# Power_Amp_V2_0.net
KiCad netlist of a schematic drawn in EAGLE
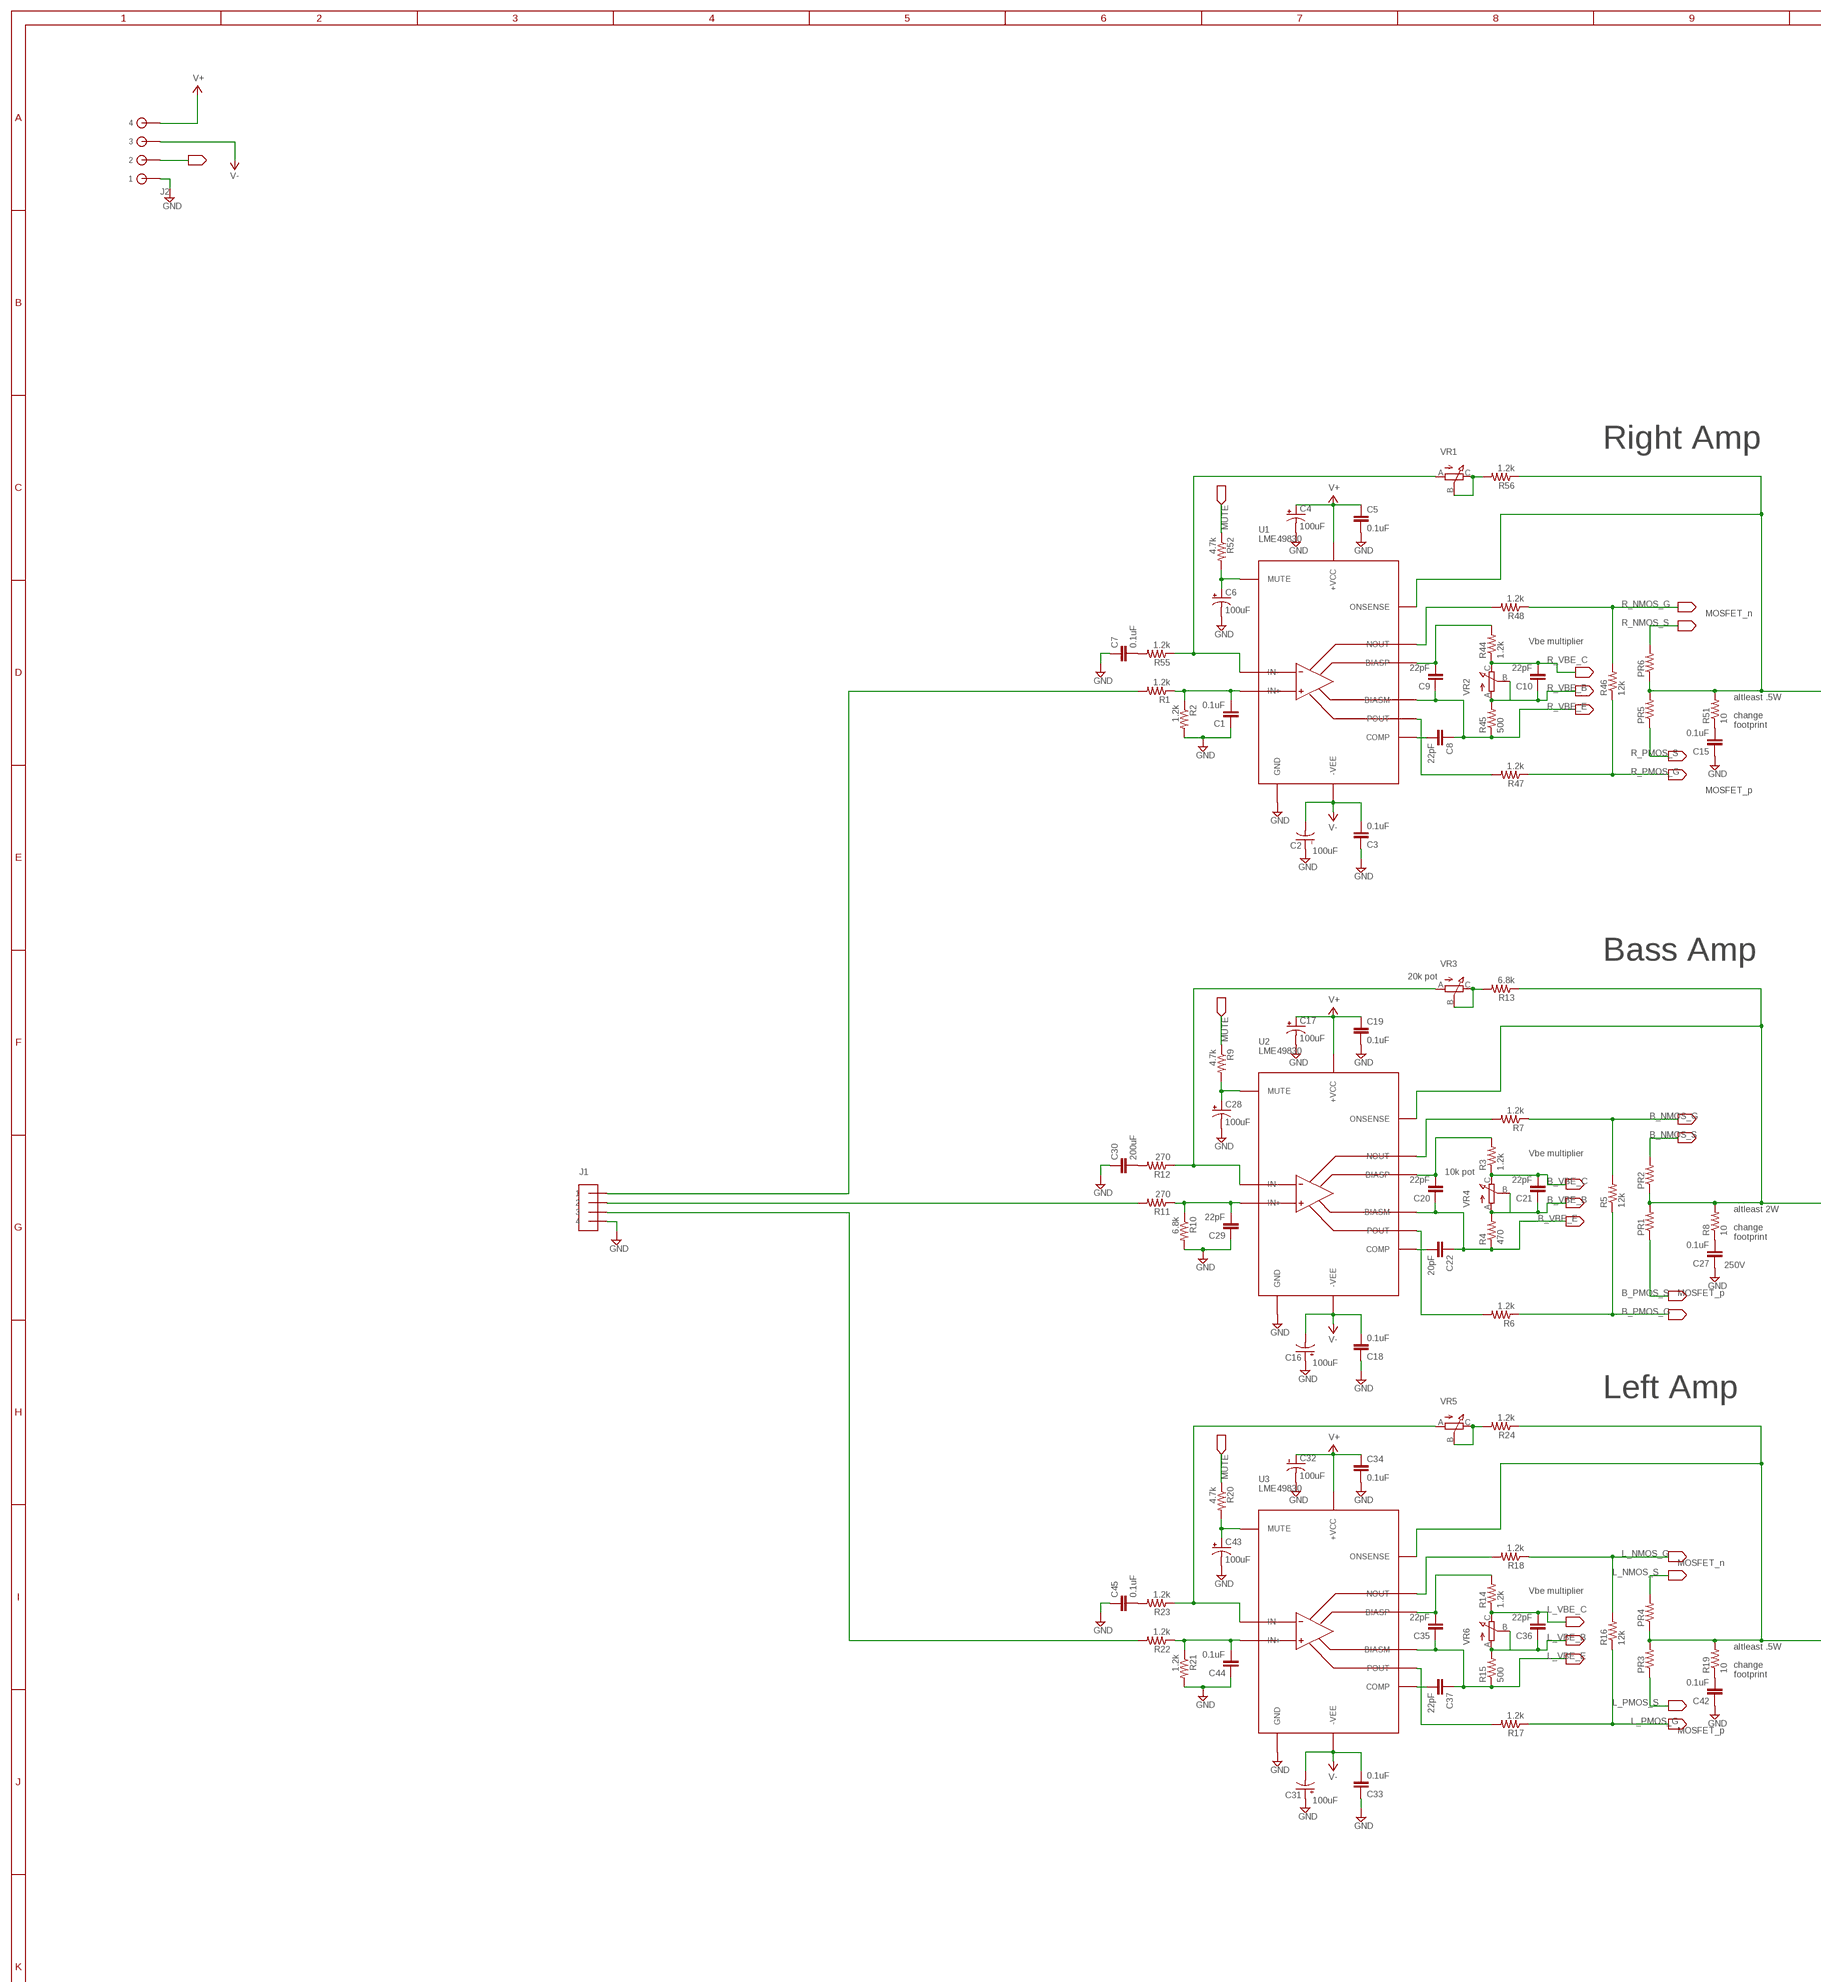
[diagram p0: schematic, sheet 1, part 1 of 3]
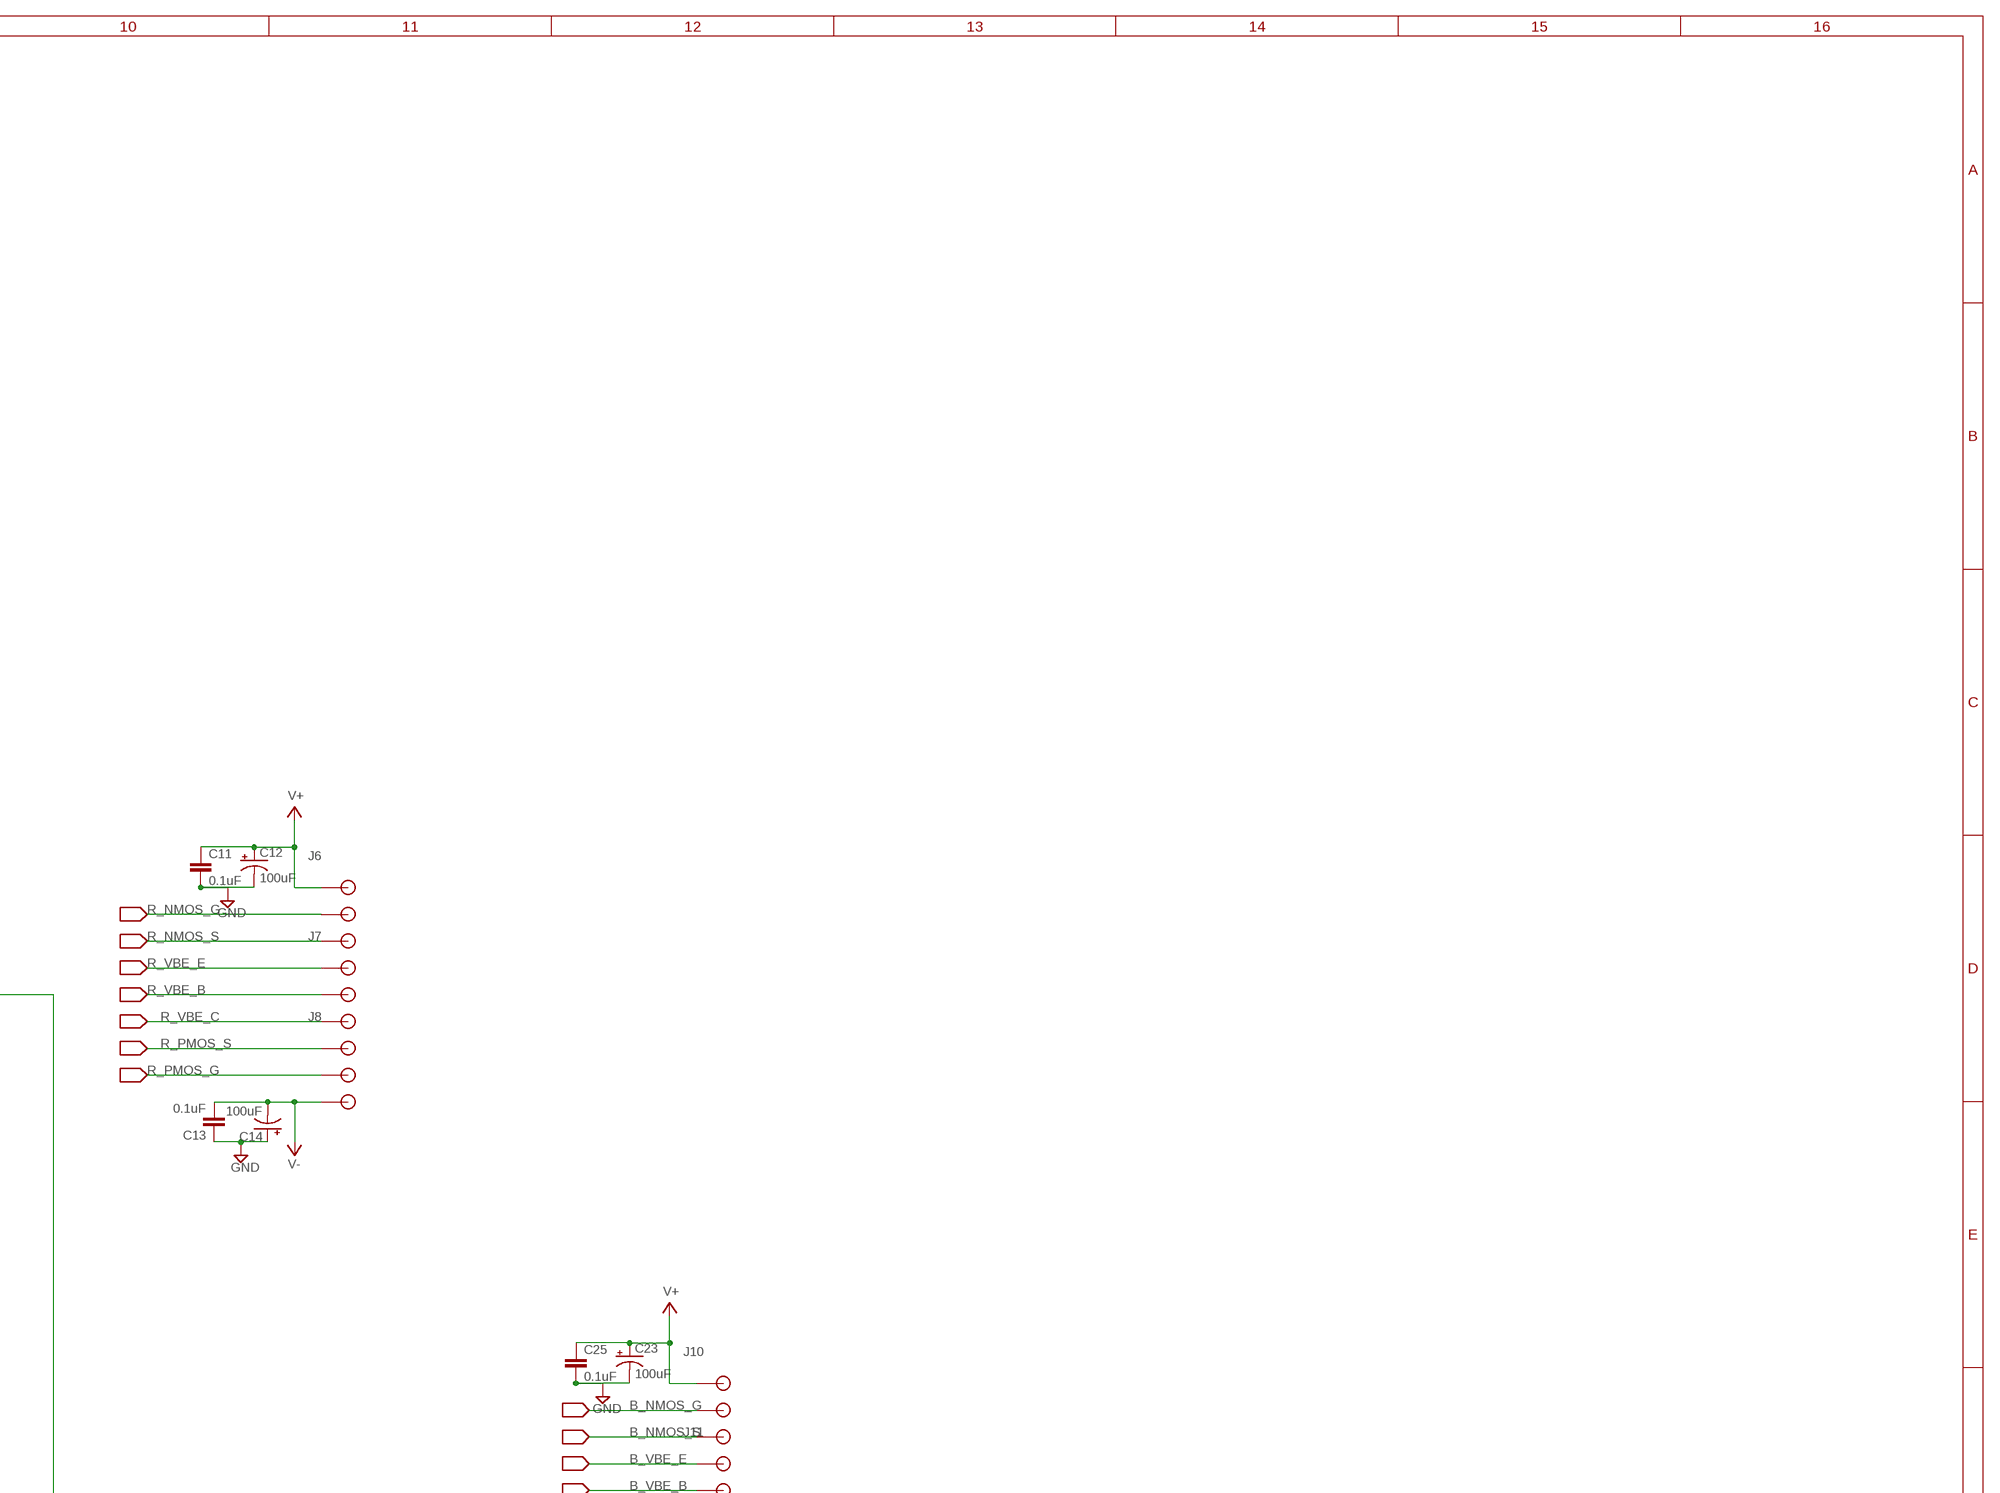
[diagram p1: schematic, sheet 1, part 2 of 3]
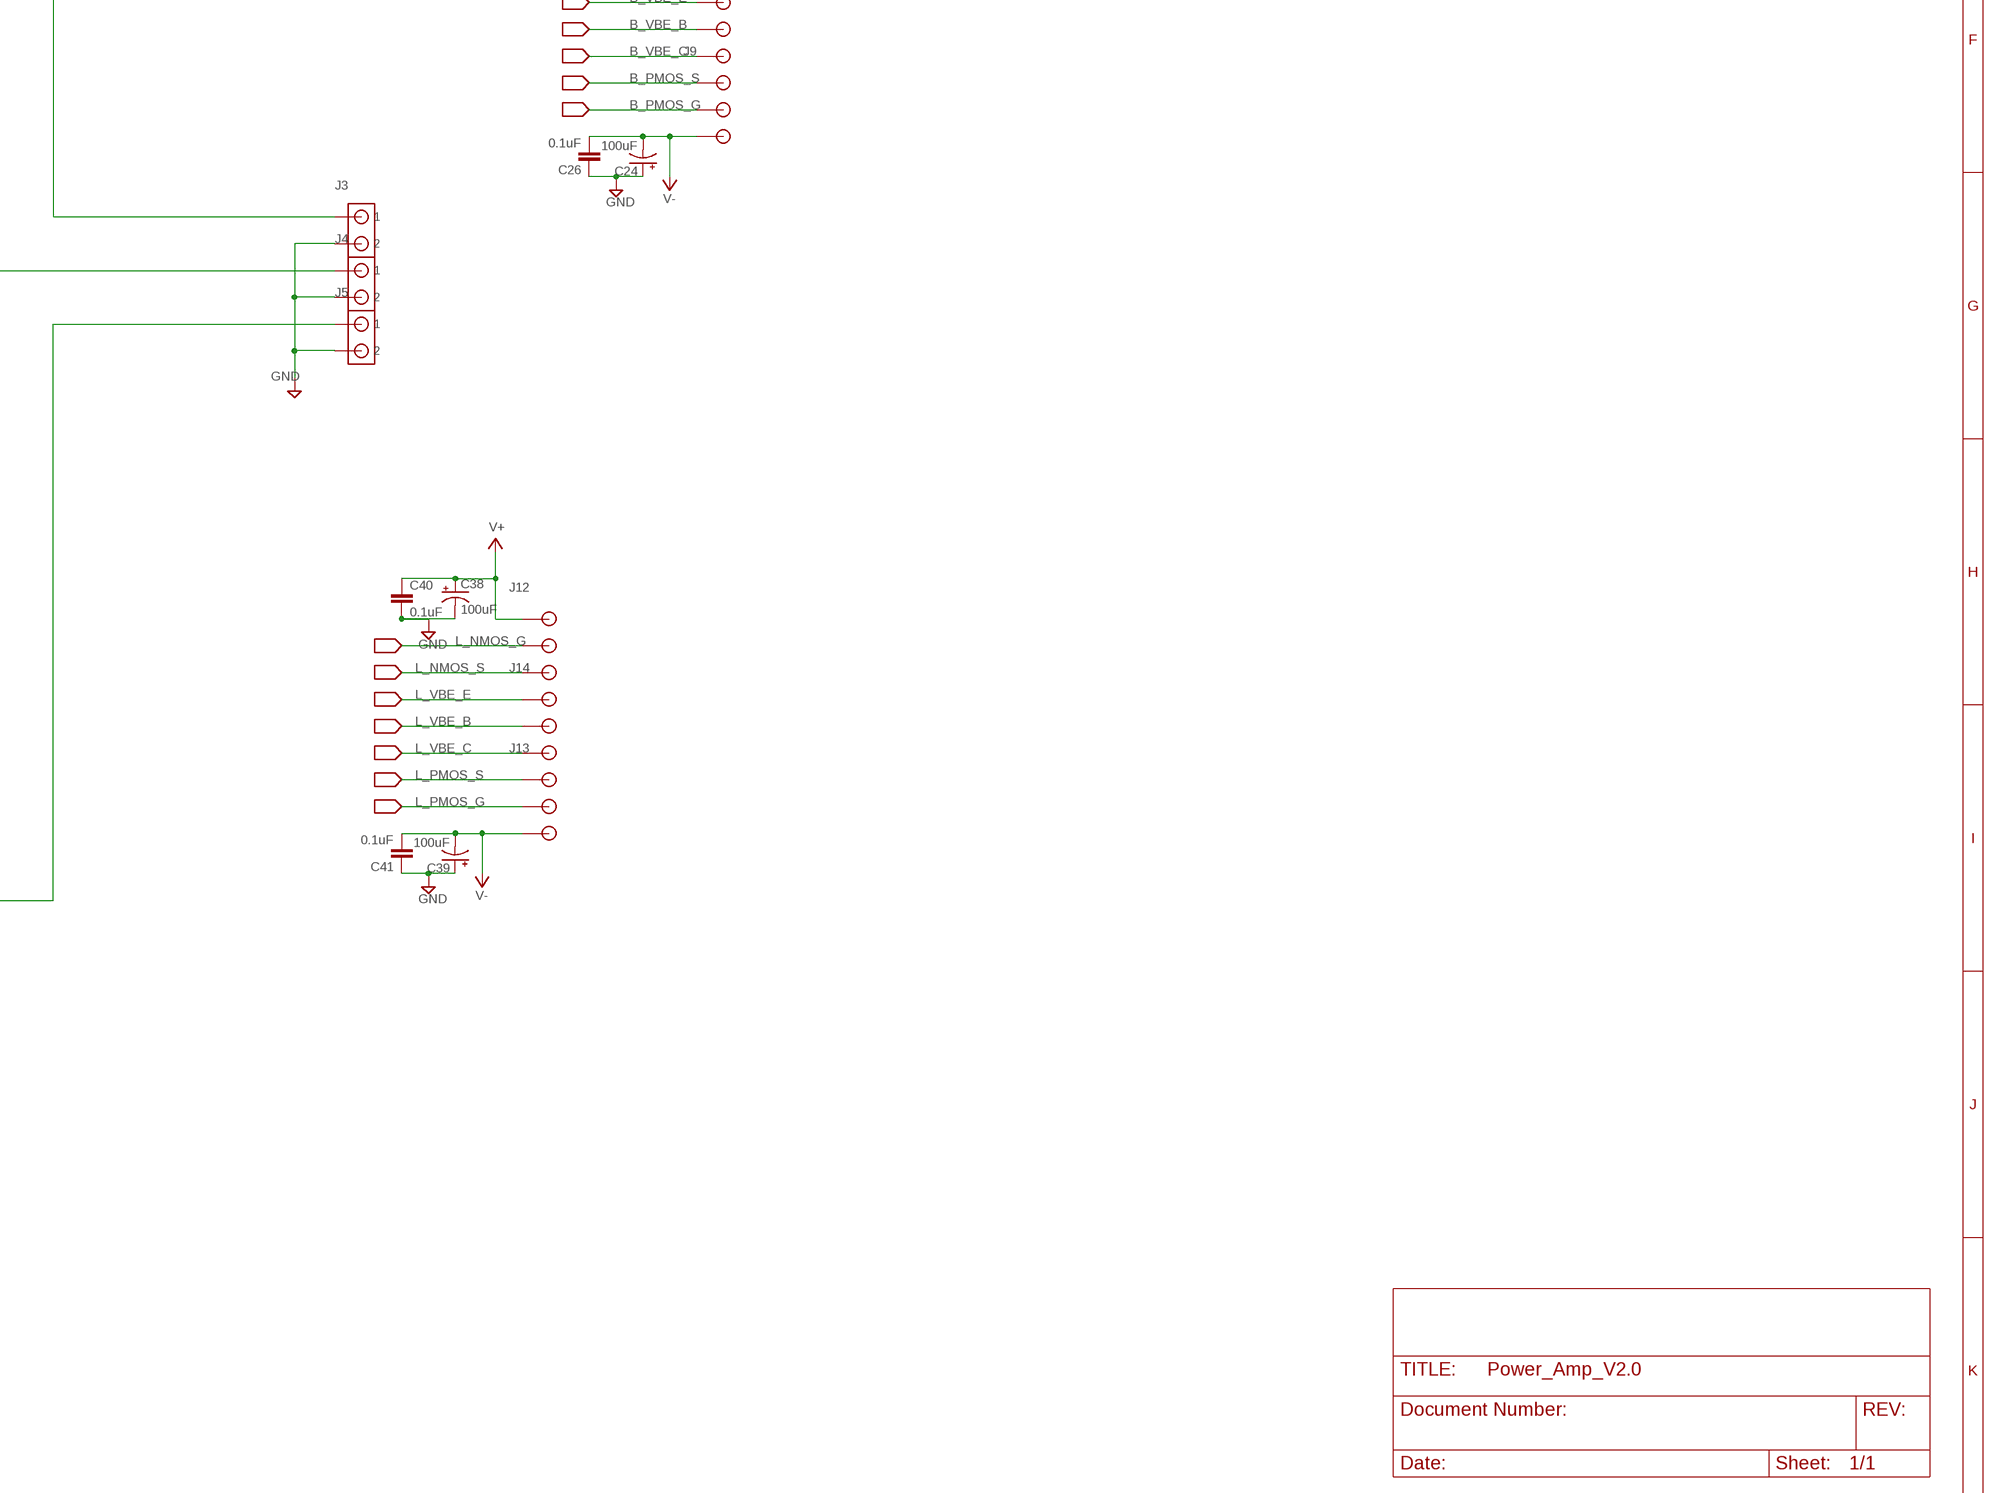
[diagram p2: schematic, sheet 1, part 3 of 3]

(export (version "E")
  (design (tool "Eeschema 10.0.6"))
  (components
    (comp (ref "C1")
      (value "0.1uF")
      (footprint "eagle-import:C050-024X044")
      (libsource (lib "eagle-import") (part "C-EU050-024X044"))
    )
    (comp (ref "C2")
      (value "100uF")
      (footprint "eagle-import:E2,5-6")
      (libsource (lib "eagle-import") (part "CPOL-USE2.5-6"))
    )
    (comp (ref "C3")
      (value "0.1uF")
      (footprint "eagle-import:C050-024X044")
      (libsource (lib "eagle-import") (part "C-EU050-024X044"))
    )
    (comp (ref "C4")
      (value "100uF")
      (footprint "eagle-import:E2,5-6")
      (libsource (lib "eagle-import") (part "CPOL-USE2.5-6"))
    )
    (comp (ref "C5")
      (value "0.1uF")
      (footprint "eagle-import:C050-024X044")
      (libsource (lib "eagle-import") (part "C-EU050-024X044"))
    )
    (comp (ref "C6")
      (value "100uF")
      (footprint "eagle-import:E2,5-6")
      (libsource (lib "eagle-import") (part "CPOL-USE2.5-6"))
    )
    (comp (ref "C7")
      (value "0.1uF")
      (footprint "eagle-import:C050-024X044")
      (libsource (lib "eagle-import") (part "C-EU050-024X044"))
    )
    (comp (ref "C8")
      (value "22pF")
      (footprint "eagle-import:C050-024X044")
      (libsource (lib "eagle-import") (part "C-EU050-024X044"))
    )
    (comp (ref "C9")
      (value "22pF")
      (footprint "eagle-import:C050-024X044")
      (libsource (lib "eagle-import") (part "C-EU050-024X044"))
    )
    (comp (ref "C10")
      (value "22pF")
      (footprint "eagle-import:C050-024X044")
      (libsource (lib "eagle-import") (part "C-EU050-024X044"))
    )
    (comp (ref "C11")
      (value "0.1uF")
      (footprint "eagle-import:C050-024X044")
      (libsource (lib "eagle-import") (part "C-EU050-024X044"))
    )
    (comp (ref "C12")
      (value "100uF")
      (footprint "eagle-import:E2,5-6")
      (libsource (lib "eagle-import") (part "CPOL-USE2.5-6"))
    )
    (comp (ref "C13")
      (value "0.1uF")
      (footprint "eagle-import:C050-024X044")
      (libsource (lib "eagle-import") (part "C-EU050-024X044"))
    )
    (comp (ref "C14")
      (value "100uF")
      (footprint "eagle-import:E2,5-6")
      (libsource (lib "eagle-import") (part "CPOL-USE2.5-6"))
    )
    (comp (ref "C15")
      (value "0.1uF")
      (footprint "eagle-import:C050-024X044")
      (libsource (lib "eagle-import") (part "C-EU050-024X044"))
    )
    (comp (ref "C16")
      (value "100uF")
      (footprint "eagle-import:E2,5-6")
      (libsource (lib "eagle-import") (part "CPOL-USE2.5-6"))
    )
    (comp (ref "C17")
      (value "100uF")
      (footprint "eagle-import:E2,5-6")
      (libsource (lib "eagle-import") (part "CPOL-USE2.5-6"))
    )
    (comp (ref "C18")
      (value "0.1uF")
      (footprint "eagle-import:C050-024X044")
      (libsource (lib "eagle-import") (part "C-EU050-024X044"))
    )
    (comp (ref "C19")
      (value "0.1uF")
      (footprint "eagle-import:C050-024X044")
      (libsource (lib "eagle-import") (part "C-EU050-024X044"))
    )
    (comp (ref "C20")
      (value "22pF")
      (footprint "eagle-import:C050-024X044")
      (libsource (lib "eagle-import") (part "C-EU050-024X044"))
    )
    (comp (ref "C21")
      (value "22pF")
      (footprint "eagle-import:C050-024X044")
      (libsource (lib "eagle-import") (part "C-EU050-024X044"))
    )
    (comp (ref "C22")
      (value "20pF")
      (footprint "eagle-import:C050-024X044")
      (libsource (lib "eagle-import") (part "C-EU050-024X044"))
    )
    (comp (ref "C23")
      (value "100uF")
      (footprint "eagle-import:E2,5-6")
      (libsource (lib "eagle-import") (part "CPOL-USE2.5-6"))
    )
    (comp (ref "C24")
      (value "100uF")
      (footprint "eagle-import:E2,5-6")
      (libsource (lib "eagle-import") (part "CPOL-USE2.5-6"))
    )
    (comp (ref "C25")
      (value "0.1uF")
      (footprint "eagle-import:C050-024X044")
      (libsource (lib "eagle-import") (part "C-EU050-024X044"))
    )
    (comp (ref "C26")
      (value "0.1uF")
      (footprint "eagle-import:C050-024X044")
      (libsource (lib "eagle-import") (part "C-EU050-024X044"))
    )
    (comp (ref "C27")
      (value "0.1uF")
      (footprint "eagle-import:C050-024X044")
      (libsource (lib "eagle-import") (part "C-EU050-024X044"))
    )
    (comp (ref "C28")
      (value "100uF")
      (footprint "eagle-import:E2,5-6")
      (libsource (lib "eagle-import") (part "CPOL-USE2.5-6"))
    )
    (comp (ref "C29")
      (value "22pF")
      (footprint "eagle-import:C050-024X044")
      (libsource (lib "eagle-import") (part "C-EU050-024X044"))
    )
    (comp (ref "C30")
      (value "200uF")
      (footprint "eagle-import:C050-024X044")
      (libsource (lib "eagle-import") (part "C-EU050-024X044"))
    )
    (comp (ref "C31")
      (value "100uF")
      (footprint "eagle-import:E2,5-6")
      (libsource (lib "eagle-import") (part "CPOL-USE2.5-6"))
    )
    (comp (ref "C32")
      (value "100uF")
      (footprint "eagle-import:E2,5-6")
      (libsource (lib "eagle-import") (part "CPOL-USE2.5-6"))
    )
    (comp (ref "C33")
      (value "0.1uF")
      (footprint "eagle-import:C050-024X044")
      (libsource (lib "eagle-import") (part "C-EU050-024X044"))
    )
    (comp (ref "C34")
      (value "0.1uF")
      (footprint "eagle-import:C050-024X044")
      (libsource (lib "eagle-import") (part "C-EU050-024X044"))
    )
    (comp (ref "C35")
      (value "22pF")
      (footprint "eagle-import:C050-024X044")
      (libsource (lib "eagle-import") (part "C-EU050-024X044"))
    )
    (comp (ref "C36")
      (value "22pF")
      (footprint "eagle-import:C050-024X044")
      (libsource (lib "eagle-import") (part "C-EU050-024X044"))
    )
    (comp (ref "C37")
      (value "22pF")
      (footprint "eagle-import:C050-024X044")
      (libsource (lib "eagle-import") (part "C-EU050-024X044"))
    )
    (comp (ref "C38")
      (value "100uF")
      (footprint "eagle-import:E2,5-6")
      (libsource (lib "eagle-import") (part "CPOL-USE2.5-6"))
    )
    (comp (ref "C39")
      (value "100uF")
      (footprint "eagle-import:E2,5-6")
      (libsource (lib "eagle-import") (part "CPOL-USE2.5-6"))
    )
    (comp (ref "C40")
      (value "0.1uF")
      (footprint "eagle-import:C050-024X044")
      (libsource (lib "eagle-import") (part "C-EU050-024X044"))
    )
    (comp (ref "C41")
      (value "0.1uF")
      (footprint "eagle-import:C050-024X044")
      (libsource (lib "eagle-import") (part "C-EU050-024X044"))
    )
    (comp (ref "C42")
      (value "0.1uF")
      (footprint "eagle-import:C050-024X044")
      (libsource (lib "eagle-import") (part "C-EU050-024X044"))
    )
    (comp (ref "C43")
      (value "100uF")
      (footprint "eagle-import:E2,5-6")
      (libsource (lib "eagle-import") (part "CPOL-USE2.5-6"))
    )
    (comp (ref "C44")
      (value "0.1uF")
      (footprint "eagle-import:C050-024X044")
      (libsource (lib "eagle-import") (part "C-EU050-024X044"))
    )
    (comp (ref "C45")
      (value "0.1uF")
      (footprint "eagle-import:C050-024X044")
      (libsource (lib "eagle-import") (part "C-EU050-024X044"))
    )
    (comp (ref "J1")
      (value "4_PIN_AMPCONN")
      (footprint "eagle-import:4_PIN_AMPCON")
      (libsource (lib "eagle-import") (part "4_PIN_AMPCONN"))
    )
    (comp (ref "J2")
      (value "1984633")
      (footprint "eagle-import:1984633")
      (libsource (lib "eagle-import") (part "1984633"))
    )
    (comp (ref "J3")
      (value "2TERMINAL_SPEAKER")
      (footprint "eagle-import:2TERMINAL_SPEAKER")
      (libsource (lib "eagle-import") (part "2TERMINAL_SPEAKER"))
    )
    (comp (ref "J4")
      (value "2TERMINAL_SPEAKER")
      (footprint "eagle-import:2TERMINAL_SPEAKER")
      (libsource (lib "eagle-import") (part "2TERMINAL_SPEAKER"))
    )
    (comp (ref "J5")
      (value "2TERMINAL_SPEAKER")
      (footprint "eagle-import:2TERMINAL_SPEAKER")
      (libsource (lib "eagle-import") (part "2TERMINAL_SPEAKER"))
    )
    (comp (ref "J6")
      (value "OSTVN03A150")
      (footprint "eagle-import:OSTVN03A150")
      (libsource (lib "eagle-import") (part "OSTVN03A150"))
    )
    (comp (ref "J7")
      (value "OSTVN03A150")
      (footprint "eagle-import:OSTVN03A150")
      (libsource (lib "eagle-import") (part "OSTVN03A150"))
    )
    (comp (ref "J8")
      (value "OSTVN03A150")
      (footprint "eagle-import:OSTVN03A150")
      (libsource (lib "eagle-import") (part "OSTVN03A150"))
    )
    (comp (ref "J9")
      (value "OSTVN03A150")
      (footprint "eagle-import:OSTVN03A150")
      (libsource (lib "eagle-import") (part "OSTVN03A150"))
    )
    (comp (ref "J10")
      (value "OSTVN03A150")
      (footprint "eagle-import:OSTVN03A150")
      (libsource (lib "eagle-import") (part "OSTVN03A150"))
    )
    (comp (ref "J11")
      (value "OSTVN03A150")
      (footprint "eagle-import:OSTVN03A150")
      (libsource (lib "eagle-import") (part "OSTVN03A150"))
    )
    (comp (ref "J12")
      (value "OSTVN03A150")
      (footprint "eagle-import:OSTVN03A150")
      (libsource (lib "eagle-import") (part "OSTVN03A150"))
    )
    (comp (ref "J13")
      (value "OSTVN03A150")
      (footprint "eagle-import:OSTVN03A150")
      (libsource (lib "eagle-import") (part "OSTVN03A150"))
    )
    (comp (ref "J14")
      (value "OSTVN03A150")
      (footprint "eagle-import:OSTVN03A150")
      (libsource (lib "eagle-import") (part "OSTVN03A150"))
    )
    (comp (ref "PR1")
      (value "R-US_0617/5V")
      (footprint "eagle-import:0617V")
      (libsource (lib "eagle-import") (part "R-US_0617/5V"))
    )
    (comp (ref "PR2")
      (value "R-US_0617/5V")
      (footprint "eagle-import:0617V")
      (libsource (lib "eagle-import") (part "R-US_0617/5V"))
    )
    (comp (ref "PR3")
      (value "R-US_0617/5V")
      (footprint "eagle-import:0617V")
      (libsource (lib "eagle-import") (part "R-US_0617/5V"))
    )
    (comp (ref "PR4")
      (value "R-US_0617/5V")
      (footprint "eagle-import:0617V")
      (libsource (lib "eagle-import") (part "R-US_0617/5V"))
    )
    (comp (ref "PR5")
      (value "R-US_0617/5V")
      (footprint "eagle-import:0617V")
      (libsource (lib "eagle-import") (part "R-US_0617/5V"))
    )
    (comp (ref "PR6")
      (value "R-US_0617/5V")
      (footprint "eagle-import:0617V")
      (libsource (lib "eagle-import") (part "R-US_0617/5V"))
    )
    (comp (ref "R1")
      (value "1.2k")
      (footprint "eagle-import:0204V")
      (libsource (lib "eagle-import") (part "R-US_0204/2V"))
    )
    (comp (ref "R2")
      (value "1.2k")
      (footprint "eagle-import:0204V")
      (libsource (lib "eagle-import") (part "R-US_0204/2V"))
    )
    (comp (ref "R3")
      (value "1.2k")
      (footprint "eagle-import:0204V")
      (libsource (lib "eagle-import") (part "R-US_0204/2V"))
    )
    (comp (ref "R4")
      (value "470")
      (footprint "eagle-import:0204V")
      (libsource (lib "eagle-import") (part "R-US_0204/2V"))
    )
    (comp (ref "R5")
      (value "12k")
      (footprint "eagle-import:0204V")
      (libsource (lib "eagle-import") (part "R-US_0204/2V"))
    )
    (comp (ref "R6")
      (value "1.2k")
      (footprint "eagle-import:0204V")
      (libsource (lib "eagle-import") (part "R-US_0204/2V"))
    )
    (comp (ref "R7")
      (value "1.2k")
      (footprint "eagle-import:0204V")
      (libsource (lib "eagle-import") (part "R-US_0204/2V"))
    )
    (comp (ref "R8")
      (value "10")
      (footprint "eagle-import:0309V")
      (libsource (lib "eagle-import") (part "R-US_0309/V"))
    )
    (comp (ref "R9")
      (value "4.7k")
      (footprint "eagle-import:0204V")
      (libsource (lib "eagle-import") (part "R-US_0204/2V"))
    )
    (comp (ref "R10")
      (value "6.8k")
      (footprint "eagle-import:0204V")
      (libsource (lib "eagle-import") (part "R-US_0204/2V"))
    )
    (comp (ref "R11")
      (value "270")
      (footprint "eagle-import:0204V")
      (libsource (lib "eagle-import") (part "R-US_0204/2V"))
    )
    (comp (ref "R12")
      (value "270")
      (footprint "eagle-import:0204V")
      (libsource (lib "eagle-import") (part "R-US_0204/2V"))
    )
    (comp (ref "R13")
      (value "6.8k")
      (footprint "eagle-import:0204V")
      (libsource (lib "eagle-import") (part "R-US_0204/2V"))
    )
    (comp (ref "R14")
      (value "1.2k")
      (footprint "eagle-import:0204V")
      (libsource (lib "eagle-import") (part "R-US_0204/2V"))
    )
    (comp (ref "R15")
      (value "500")
      (footprint "eagle-import:0204V")
      (libsource (lib "eagle-import") (part "R-US_0204/2V"))
    )
    (comp (ref "R16")
      (value "12k")
      (footprint "eagle-import:0204V")
      (libsource (lib "eagle-import") (part "R-US_0204/2V"))
    )
    (comp (ref "R17")
      (value "1.2k")
      (footprint "eagle-import:0204V")
      (libsource (lib "eagle-import") (part "R-US_0204/2V"))
    )
    (comp (ref "R18")
      (value "1.2k")
      (footprint "eagle-import:0204V")
      (libsource (lib "eagle-import") (part "R-US_0204/2V"))
    )
    (comp (ref "R19")
      (value "10")
      (footprint "eagle-import:0309V")
      (libsource (lib "eagle-import") (part "R-US_0309/V"))
    )
    (comp (ref "R20")
      (value "4.7k")
      (footprint "eagle-import:0204V")
      (libsource (lib "eagle-import") (part "R-US_0204/2V"))
    )
    (comp (ref "R21")
      (value "1.2k")
      (footprint "eagle-import:0204V")
      (libsource (lib "eagle-import") (part "R-US_0204/2V"))
    )
    (comp (ref "R22")
      (value "1.2k")
      (footprint "eagle-import:0204V")
      (libsource (lib "eagle-import") (part "R-US_0204/2V"))
    )
    (comp (ref "R23")
      (value "1.2k")
      (footprint "eagle-import:0204V")
      (libsource (lib "eagle-import") (part "R-US_0204/2V"))
    )
    (comp (ref "R24")
      (value "1.2k")
      (footprint "eagle-import:0204V")
      (libsource (lib "eagle-import") (part "R-US_0204/2V"))
    )
    (comp (ref "R44")
      (value "1.2k")
      (footprint "eagle-import:0204V")
      (libsource (lib "eagle-import") (part "R-US_0204/2V"))
    )
    (comp (ref "R45")
      (value "500")
      (footprint "eagle-import:0204V")
      (libsource (lib "eagle-import") (part "R-US_0204/2V"))
    )
    (comp (ref "R46")
      (value "12k")
      (footprint "eagle-import:0204V")
      (libsource (lib "eagle-import") (part "R-US_0204/2V"))
    )
    (comp (ref "R47")
      (value "1.2k")
      (footprint "eagle-import:0204V")
      (libsource (lib "eagle-import") (part "R-US_0204/2V"))
    )
    (comp (ref "R48")
      (value "1.2k")
      (footprint "eagle-import:0204V")
      (libsource (lib "eagle-import") (part "R-US_0204/2V"))
    )
    (comp (ref "R51")
      (value "10")
      (footprint "eagle-import:0309V")
      (libsource (lib "eagle-import") (part "R-US_0309/V"))
    )
    (comp (ref "R52")
      (value "4.7k")
      (footprint "eagle-import:0204V")
      (libsource (lib "eagle-import") (part "R-US_0204/2V"))
    )
    (comp (ref "R55")
      (value "1.2k")
      (footprint "eagle-import:0204V")
      (libsource (lib "eagle-import") (part "R-US_0204/2V"))
    )
    (comp (ref "R56")
      (value "1.2k")
      (footprint "eagle-import:0204V")
      (libsource (lib "eagle-import") (part "R-US_0204/2V"))
    )
    (comp (ref "U1")
      (value "LME49830")
      (footprint "eagle-import:NDN0015A")
      (libsource (lib "eagle-import") (part "LME49830"))
    )
    (comp (ref "U2")
      (value "LME49830")
      (footprint "eagle-import:NDN0015A")
      (libsource (lib "eagle-import") (part "LME49830"))
    )
    (comp (ref "U3")
      (value "LME49830")
      (footprint "eagle-import:NDN0015A")
      (libsource (lib "eagle-import") (part "LME49830"))
    )
    (comp (ref "VR1")
      (value "EVM2W")
      (footprint "eagle-import:EVM2W")
      (libsource (lib "eagle-import") (part "EVM2W"))
    )
    (comp (ref "VR2")
      (value "EVM2W")
      (footprint "eagle-import:EVM2W")
      (libsource (lib "eagle-import") (part "EVM2W"))
    )
    (comp (ref "VR3")
      (value "EVM2W")
      (footprint "eagle-import:EVM2W")
      (libsource (lib "eagle-import") (part "EVM2W"))
    )
    (comp (ref "VR4")
      (value "EVM2W")
      (footprint "eagle-import:EVM2W")
      (libsource (lib "eagle-import") (part "EVM2W"))
    )
    (comp (ref "VR5")
      (value "EVM2W")
      (footprint "eagle-import:EVM2W")
      (libsource (lib "eagle-import") (part "EVM2W"))
    )
    (comp (ref "VR6")
      (value "EVM2W")
      (footprint "eagle-import:EVM2W")
      (libsource (lib "eagle-import") (part "EVM2W"))
    )
  )
  (nets
    (net (code "1") (name "/B_NMOS_G") (class "Default")
      (node (ref "J10") (pin "P$2") (pinfunction "2_P$2") (pintype "bidirectional"))
      (node (ref "R5") (pin "2") (pinfunction "2_2") (pintype "passive"))
      (node (ref "R7") (pin "1") (pinfunction "1_1") (pintype "passive"))
    )
    (net (code "2") (name "/B_NMOS_S") (class "Default")
      (node (ref "J10") (pin "P$3") (pinfunction "3_P$3") (pintype "bidirectional"))
      (node (ref "PR2") (pin "2") (pinfunction "2_2") (pintype "passive"))
    )
    (net (code "3") (name "/B_PMOS_G") (class "Default")
      (node (ref "J9") (pin "P$2") (pinfunction "2_P$2") (pintype "bidirectional"))
      (node (ref "R5") (pin "1") (pinfunction "1_1") (pintype "passive"))
      (node (ref "R6") (pin "1") (pinfunction "1_1") (pintype "passive"))
    )
    (net (code "4") (name "/B_PMOS_S") (class "Default")
      (node (ref "J9") (pin "P$1") (pinfunction "1_P$1") (pintype "bidirectional"))
      (node (ref "PR1") (pin "1") (pinfunction "1_1") (pintype "passive"))
    )
    (net (code "5") (name "/B_VBE_B") (class "Default")
      (node (ref "C21") (pin "1") (pinfunction "1_1") (pintype "passive"))
      (node (ref "J11") (pin "P$2") (pinfunction "2_P$2") (pintype "bidirectional"))
      (node (ref "R4") (pin "2") (pinfunction "2_2") (pintype "passive"))
      (node (ref "VR4") (pin "A") (pinfunction "A_A") (pintype "passive"))
      (node (ref "VR4") (pin "B") (pinfunction "B_B") (pintype "passive"))
    )
    (net (code "6") (name "/B_VBE_C") (class "Default")
      (node (ref "C21") (pin "2") (pinfunction "2_2") (pintype "passive"))
      (node (ref "J11") (pin "P$3") (pinfunction "3_P$3") (pintype "bidirectional"))
      (node (ref "R3") (pin "1") (pinfunction "1_1") (pintype "passive"))
      (node (ref "VR4") (pin "C") (pinfunction "C_C") (pintype "passive"))
    )
    (net (code "7") (name "/B_VBE_E") (class "Default")
      (node (ref "C20") (pin "1") (pinfunction "1_1") (pintype "passive"))
      (node (ref "C22") (pin "1") (pinfunction "1_1") (pintype "passive"))
      (node (ref "J11") (pin "P$1") (pinfunction "1_P$1") (pintype "bidirectional"))
      (node (ref "R4") (pin "1") (pinfunction "1_1") (pintype "passive"))
      (node (ref "U2") (pin "P11") (pinfunction "BIASM_P11") (pintype "bidirectional"))
    )
    (net (code "8") (name "/L_NMOS_G") (class "Default")
      (node (ref "J12") (pin "P$2") (pinfunction "2_P$2") (pintype "bidirectional"))
      (node (ref "R16") (pin "2") (pinfunction "2_2") (pintype "passive"))
      (node (ref "R18") (pin "1") (pinfunction "1_1") (pintype "passive"))
    )
    (net (code "9") (name "/L_NMOS_S") (class "Default")
      (node (ref "J12") (pin "P$3") (pinfunction "3_P$3") (pintype "bidirectional"))
      (node (ref "PR4") (pin "2") (pinfunction "2_2") (pintype "passive"))
    )
    (net (code "10") (name "/L_PMOS_G") (class "Default")
      (node (ref "J13") (pin "P$2") (pinfunction "2_P$2") (pintype "bidirectional"))
      (node (ref "R16") (pin "1") (pinfunction "1_1") (pintype "passive"))
      (node (ref "R17") (pin "1") (pinfunction "1_1") (pintype "passive"))
    )
    (net (code "11") (name "/L_PMOS_S") (class "Default")
      (node (ref "J13") (pin "P$1") (pinfunction "1_P$1") (pintype "bidirectional"))
      (node (ref "PR3") (pin "1") (pinfunction "1_1") (pintype "passive"))
    )
    (net (code "12") (name "/L_VBE_B") (class "Default")
      (node (ref "C36") (pin "1") (pinfunction "1_1") (pintype "passive"))
      (node (ref "J14") (pin "P$2") (pinfunction "2_P$2") (pintype "bidirectional"))
      (node (ref "R15") (pin "2") (pinfunction "2_2") (pintype "passive"))
      (node (ref "VR6") (pin "A") (pinfunction "A_A") (pintype "passive"))
      (node (ref "VR6") (pin "B") (pinfunction "B_B") (pintype "passive"))
    )
    (net (code "13") (name "/L_VBE_C") (class "Default")
      (node (ref "C36") (pin "2") (pinfunction "2_2") (pintype "passive"))
      (node (ref "J14") (pin "P$3") (pinfunction "3_P$3") (pintype "bidirectional"))
      (node (ref "R14") (pin "1") (pinfunction "1_1") (pintype "passive"))
      (node (ref "VR6") (pin "C") (pinfunction "C_C") (pintype "passive"))
    )
    (net (code "14") (name "/L_VBE_E") (class "Default")
      (node (ref "C35") (pin "1") (pinfunction "1_1") (pintype "passive"))
      (node (ref "C37") (pin "1") (pinfunction "1_1") (pintype "passive"))
      (node (ref "J14") (pin "P$1") (pinfunction "1_P$1") (pintype "bidirectional"))
      (node (ref "R15") (pin "1") (pinfunction "1_1") (pintype "passive"))
      (node (ref "U3") (pin "P11") (pinfunction "BIASM_P11") (pintype "bidirectional"))
    )
    (net (code "15") (name "/MUTE") (class "Default")
      (node (ref "J2") (pin "P$2") (pinfunction "2_P$2") (pintype "passive"))
      (node (ref "R20") (pin "1") (pinfunction "1_1") (pintype "passive"))
      (node (ref "R52") (pin "1") (pinfunction "1_1") (pintype "passive"))
      (node (ref "R9") (pin "1") (pinfunction "1_1") (pintype "passive"))
    )
    (net (code "16") (name "/R_NMOS_G") (class "Default")
      (node (ref "J6") (pin "P$2") (pinfunction "2_P$2") (pintype "bidirectional"))
      (node (ref "R46") (pin "2") (pinfunction "2_2") (pintype "passive"))
      (node (ref "R48") (pin "1") (pinfunction "1_1") (pintype "passive"))
    )
    (net (code "17") (name "/R_NMOS_S") (class "Default")
      (node (ref "J6") (pin "P$3") (pinfunction "3_P$3") (pintype "bidirectional"))
      (node (ref "PR6") (pin "2") (pinfunction "2_2") (pintype "passive"))
    )
    (net (code "18") (name "/R_PMOS_G") (class "Default")
      (node (ref "J8") (pin "P$2") (pinfunction "2_P$2") (pintype "bidirectional"))
      (node (ref "R46") (pin "1") (pinfunction "1_1") (pintype "passive"))
      (node (ref "R47") (pin "1") (pinfunction "1_1") (pintype "passive"))
    )
    (net (code "19") (name "/R_PMOS_S") (class "Default")
      (node (ref "J8") (pin "P$1") (pinfunction "1_P$1") (pintype "bidirectional"))
      (node (ref "PR5") (pin "1") (pinfunction "1_1") (pintype "passive"))
    )
    (net (code "20") (name "/R_VBE_B") (class "Default")
      (node (ref "C10") (pin "1") (pinfunction "1_1") (pintype "passive"))
      (node (ref "J7") (pin "P$2") (pinfunction "2_P$2") (pintype "bidirectional"))
      (node (ref "R45") (pin "2") (pinfunction "2_2") (pintype "passive"))
      (node (ref "VR2") (pin "A") (pinfunction "A_A") (pintype "passive"))
      (node (ref "VR2") (pin "B") (pinfunction "B_B") (pintype "passive"))
    )
    (net (code "21") (name "/R_VBE_C") (class "Default")
      (node (ref "C10") (pin "2") (pinfunction "2_2") (pintype "passive"))
      (node (ref "J7") (pin "P$3") (pinfunction "3_P$3") (pintype "bidirectional"))
      (node (ref "R44") (pin "1") (pinfunction "1_1") (pintype "passive"))
      (node (ref "VR2") (pin "C") (pinfunction "C_C") (pintype "passive"))
    )
    (net (code "22") (name "/R_VBE_E") (class "Default")
      (node (ref "C8") (pin "1") (pinfunction "1_1") (pintype "passive"))
      (node (ref "C9") (pin "1") (pinfunction "1_1") (pintype "passive"))
      (node (ref "J7") (pin "P$1") (pinfunction "1_P$1") (pintype "bidirectional"))
      (node (ref "R45") (pin "1") (pinfunction "1_1") (pintype "passive"))
      (node (ref "U1") (pin "P11") (pinfunction "BIASM_P11") (pintype "bidirectional"))
    )
    (net (code "23") (name "GND") (class "Default")
      (node (ref "C1") (pin "1") (pinfunction "1_1") (pintype "passive"))
      (node (ref "C11") (pin "2") (pinfunction "2_2") (pintype "passive"))
      (node (ref "C12") (pin "-") (pinfunction "-_-") (pintype "passive"))
      (node (ref "C13") (pin "1") (pinfunction "1_1") (pintype "passive"))
      (node (ref "C14") (pin "+") (pinfunction "+_+") (pintype "passive"))
      (node (ref "C15") (pin "1") (pinfunction "1_1") (pintype "passive"))
      (node (ref "C16") (pin "+") (pinfunction "+_+") (pintype "passive"))
      (node (ref "C17") (pin "-") (pinfunction "-_-") (pintype "passive"))
      (node (ref "C18") (pin "1") (pinfunction "1_1") (pintype "passive"))
      (node (ref "C19") (pin "2") (pinfunction "2_2") (pintype "passive"))
      (node (ref "C2") (pin "+") (pinfunction "+_+") (pintype "passive"))
      (node (ref "C23") (pin "-") (pinfunction "-_-") (pintype "passive"))
      (node (ref "C24") (pin "+") (pinfunction "+_+") (pintype "passive"))
      (node (ref "C25") (pin "2") (pinfunction "2_2") (pintype "passive"))
      (node (ref "C26") (pin "1") (pinfunction "1_1") (pintype "passive"))
      (node (ref "C27") (pin "1") (pinfunction "1_1") (pintype "passive"))
      (node (ref "C28") (pin "-") (pinfunction "-_-") (pintype "passive"))
      (node (ref "C29") (pin "1") (pinfunction "1_1") (pintype "passive"))
      (node (ref "C3") (pin "1") (pinfunction "1_1") (pintype "passive"))
      (node (ref "C30") (pin "1") (pinfunction "1_1") (pintype "passive"))
      (node (ref "C31") (pin "+") (pinfunction "+_+") (pintype "passive"))
      (node (ref "C32") (pin "-") (pinfunction "-_-") (pintype "passive"))
      (node (ref "C33") (pin "1") (pinfunction "1_1") (pintype "passive"))
      (node (ref "C34") (pin "2") (pinfunction "2_2") (pintype "passive"))
      (node (ref "C38") (pin "-") (pinfunction "-_-") (pintype "passive"))
      (node (ref "C39") (pin "+") (pinfunction "+_+") (pintype "passive"))
      (node (ref "C4") (pin "-") (pinfunction "-_-") (pintype "passive"))
      (node (ref "C40") (pin "2") (pinfunction "2_2") (pintype "passive"))
      (node (ref "C41") (pin "1") (pinfunction "1_1") (pintype "passive"))
      (node (ref "C42") (pin "1") (pinfunction "1_1") (pintype "passive"))
      (node (ref "C43") (pin "-") (pinfunction "-_-") (pintype "passive"))
      (node (ref "C44") (pin "1") (pinfunction "1_1") (pintype "passive"))
      (node (ref "C45") (pin "1") (pinfunction "1_1") (pintype "passive"))
      (node (ref "C5") (pin "2") (pinfunction "2_2") (pintype "passive"))
      (node (ref "C6") (pin "-") (pinfunction "-_-") (pintype "passive"))
      (node (ref "C7") (pin "1") (pinfunction "1_1") (pintype "passive"))
      (node (ref "J1") (pin "4") (pinfunction "4_4") (pintype "passive"))
      (node (ref "J2") (pin "P$1") (pinfunction "1_P$1") (pintype "passive"))
      (node (ref "J3") (pin "P$2") (pinfunction "2_P$2") (pintype "passive"))
      (node (ref "J4") (pin "P$2") (pinfunction "2_P$2") (pintype "passive"))
      (node (ref "J5") (pin "P$2") (pinfunction "2_P$2") (pintype "passive"))
      (node (ref "R10") (pin "2") (pinfunction "2_2") (pintype "passive"))
      (node (ref "R2") (pin "2") (pinfunction "2_2") (pintype "passive"))
      (node (ref "R21") (pin "2") (pinfunction "2_2") (pintype "passive"))
      (node (ref "U1") (pin "P3") (pinfunction "GND_P3") (pintype "bidirectional"))
      (node (ref "U2") (pin "P3") (pinfunction "GND_P3") (pintype "bidirectional"))
      (node (ref "U3") (pin "P3") (pinfunction "GND_P3") (pintype "bidirectional"))
    )
    (net (code "24") (name "Net-(C7-Pad2)") (class "Default")
      (node (ref "C7") (pin "2") (pinfunction "2_2") (pintype "passive"))
      (node (ref "R55") (pin "2") (pinfunction "2_2") (pintype "passive"))
    )
    (net (code "25") (name "Net-(C15-Pad2)") (class "Default")
      (node (ref "C15") (pin "2") (pinfunction "2_2") (pintype "passive"))
      (node (ref "R51") (pin "1") (pinfunction "1_1") (pintype "passive"))
    )
    (net (code "26") (name "Net-(C27-Pad2)") (class "Default")
      (node (ref "C27") (pin "2") (pinfunction "2_2") (pintype "passive"))
      (node (ref "R8") (pin "1") (pinfunction "1_1") (pintype "passive"))
    )
    (net (code "27") (name "Net-(C30-Pad2)") (class "Default")
      (node (ref "C30") (pin "2") (pinfunction "2_2") (pintype "passive"))
      (node (ref "R12") (pin "2") (pinfunction "2_2") (pintype "passive"))
    )
    (net (code "28") (name "Net-(C42-Pad2)") (class "Default")
      (node (ref "C42") (pin "2") (pinfunction "2_2") (pintype "passive"))
      (node (ref "R19") (pin "1") (pinfunction "1_1") (pintype "passive"))
    )
    (net (code "29") (name "Net-(C45-Pad2)") (class "Default")
      (node (ref "C45") (pin "2") (pinfunction "2_2") (pintype "passive"))
      (node (ref "R23") (pin "2") (pinfunction "2_2") (pintype "passive"))
    )
    (net (code "30") (name "Net-(J1-Pad1)") (class "Default")
      (node (ref "J1") (pin "1") (pinfunction "1_1") (pintype "passive"))
      (node (ref "R1") (pin "2") (pinfunction "2_2") (pintype "passive"))
    )
    (net (code "31") (name "Net-(J1-Pad2)") (class "Default")
      (node (ref "J1") (pin "2") (pinfunction "2_2") (pintype "passive"))
      (node (ref "R11") (pin "2") (pinfunction "2_2") (pintype "passive"))
    )
    (net (code "32") (name "Net-(J1-Pad3)") (class "Default")
      (node (ref "J1") (pin "3") (pinfunction "3_3") (pintype "passive"))
      (node (ref "R22") (pin "2") (pinfunction "2_2") (pintype "passive"))
    )
    (net (code "33") (name "Net-(J3-1)") (class "Default")
      (node (ref "J3") (pin "P$1") (pinfunction "1_P$1") (pintype "passive"))
      (node (ref "PR5") (pin "2") (pinfunction "2_2") (pintype "passive"))
      (node (ref "PR6") (pin "1") (pinfunction "1_1") (pintype "passive"))
      (node (ref "R51") (pin "2") (pinfunction "2_2") (pintype "passive"))
      (node (ref "R56") (pin "1") (pinfunction "1_1") (pintype "passive"))
      (node (ref "U1") (pin "P$8") (pinfunction "ONSENSE_P$8") (pintype "bidirectional"))
    )
    (net (code "34") (name "Net-(J4-1)") (class "Default")
      (node (ref "J4") (pin "P$1") (pinfunction "1_P$1") (pintype "passive"))
      (node (ref "PR1") (pin "2") (pinfunction "2_2") (pintype "passive"))
      (node (ref "PR2") (pin "1") (pinfunction "1_1") (pintype "passive"))
      (node (ref "R13") (pin "1") (pinfunction "1_1") (pintype "passive"))
      (node (ref "R8") (pin "2") (pinfunction "2_2") (pintype "passive"))
      (node (ref "U2") (pin "P$8") (pinfunction "ONSENSE_P$8") (pintype "bidirectional"))
    )
    (net (code "35") (name "Net-(J5-1)") (class "Default")
      (node (ref "J5") (pin "P$1") (pinfunction "1_P$1") (pintype "passive"))
      (node (ref "PR3") (pin "2") (pinfunction "2_2") (pintype "passive"))
      (node (ref "PR4") (pin "1") (pinfunction "1_1") (pintype "passive"))
      (node (ref "R19") (pin "2") (pinfunction "2_2") (pintype "passive"))
      (node (ref "R24") (pin "1") (pinfunction "1_1") (pintype "passive"))
      (node (ref "U3") (pin "P$8") (pinfunction "ONSENSE_P$8") (pintype "bidirectional"))
    )
    (net (code "36") (name "Net-(R13-Pad2)") (class "Default")
      (node (ref "R13") (pin "2") (pinfunction "2_2") (pintype "passive"))
      (node (ref "VR3") (pin "B") (pinfunction "B_B") (pintype "passive"))
      (node (ref "VR3") (pin "C") (pinfunction "C_C") (pintype "passive"))
    )
    (net (code "37") (name "Net-(R24-Pad2)") (class "Default")
      (node (ref "R24") (pin "2") (pinfunction "2_2") (pintype "passive"))
      (node (ref "VR5") (pin "B") (pinfunction "B_B") (pintype "passive"))
      (node (ref "VR5") (pin "C") (pinfunction "C_C") (pintype "passive"))
    )
    (net (code "38") (name "Net-(R56-Pad2)") (class "Default")
      (node (ref "R56") (pin "2") (pinfunction "2_2") (pintype "passive"))
      (node (ref "VR1") (pin "B") (pinfunction "B_B") (pintype "passive"))
      (node (ref "VR1") (pin "C") (pinfunction "C_C") (pintype "passive"))
    )
    (net (code "39") (name "Net-(U1-BIASP)") (class "Default")
      (node (ref "C9") (pin "2") (pinfunction "2_2") (pintype "passive"))
      (node (ref "R44") (pin "2") (pinfunction "2_2") (pintype "passive"))
      (node (ref "U1") (pin "P12") (pinfunction "BIASP_P12") (pintype "bidirectional"))
    )
    (net (code "40") (name "Net-(U1-COMP)") (class "Default")
      (node (ref "C8") (pin "2") (pinfunction "2_2") (pintype "passive"))
      (node (ref "U1") (pin "P6") (pinfunction "COMP_P6") (pintype "bidirectional"))
    )
    (net (code "41") (name "Net-(U1-IN+)") (class "Default")
      (node (ref "C1") (pin "2") (pinfunction "2_2") (pintype "passive"))
      (node (ref "R1") (pin "1") (pinfunction "1_1") (pintype "passive"))
      (node (ref "R2") (pin "1") (pinfunction "1_1") (pintype "passive"))
      (node (ref "U1") (pin "P4") (pinfunction "IN+_P4") (pintype "bidirectional"))
    )
    (net (code "42") (name "Net-(U1-IN-)") (class "Default")
      (node (ref "R55") (pin "1") (pinfunction "1_1") (pintype "passive"))
      (node (ref "U1") (pin "P5") (pinfunction "IN-_P5") (pintype "bidirectional"))
      (node (ref "VR1") (pin "A") (pinfunction "A_A") (pintype "passive"))
    )
    (net (code "43") (name "Net-(U1-MUTE)") (class "Default")
      (node (ref "C6") (pin "+") (pinfunction "+_+") (pintype "passive"))
      (node (ref "R52") (pin "2") (pinfunction "2_2") (pintype "passive"))
      (node (ref "U1") (pin "P2") (pinfunction "MUTE_P2") (pintype "bidirectional"))
    )
    (net (code "44") (name "Net-(U1-NOUT)") (class "Default")
      (node (ref "R48") (pin "2") (pinfunction "2_2") (pintype "passive"))
      (node (ref "U1") (pin "P14") (pinfunction "NOUT_P14") (pintype "bidirectional"))
    )
    (net (code "45") (name "Net-(U1-POUT)") (class "Default")
      (node (ref "R47") (pin "2") (pinfunction "2_2") (pintype "passive"))
      (node (ref "U1") (pin "P13") (pinfunction "POUT_P13") (pintype "bidirectional"))
    )
    (net (code "46") (name "Net-(U2-BIASP)") (class "Default")
      (node (ref "C20") (pin "2") (pinfunction "2_2") (pintype "passive"))
      (node (ref "R3") (pin "2") (pinfunction "2_2") (pintype "passive"))
      (node (ref "U2") (pin "P12") (pinfunction "BIASP_P12") (pintype "bidirectional"))
    )
    (net (code "47") (name "Net-(U2-COMP)") (class "Default")
      (node (ref "C22") (pin "2") (pinfunction "2_2") (pintype "passive"))
      (node (ref "U2") (pin "P6") (pinfunction "COMP_P6") (pintype "bidirectional"))
    )
    (net (code "48") (name "Net-(U2-IN+)") (class "Default")
      (node (ref "C29") (pin "2") (pinfunction "2_2") (pintype "passive"))
      (node (ref "R10") (pin "1") (pinfunction "1_1") (pintype "passive"))
      (node (ref "R11") (pin "1") (pinfunction "1_1") (pintype "passive"))
      (node (ref "U2") (pin "P4") (pinfunction "IN+_P4") (pintype "bidirectional"))
    )
    (net (code "49") (name "Net-(U2-IN-)") (class "Default")
      (node (ref "R12") (pin "1") (pinfunction "1_1") (pintype "passive"))
      (node (ref "U2") (pin "P5") (pinfunction "IN-_P5") (pintype "bidirectional"))
      (node (ref "VR3") (pin "A") (pinfunction "A_A") (pintype "passive"))
    )
    (net (code "50") (name "Net-(U2-MUTE)") (class "Default")
      (node (ref "C28") (pin "+") (pinfunction "+_+") (pintype "passive"))
      (node (ref "R9") (pin "2") (pinfunction "2_2") (pintype "passive"))
      (node (ref "U2") (pin "P2") (pinfunction "MUTE_P2") (pintype "bidirectional"))
    )
    (net (code "51") (name "Net-(U2-NOUT)") (class "Default")
      (node (ref "R7") (pin "2") (pinfunction "2_2") (pintype "passive"))
      (node (ref "U2") (pin "P14") (pinfunction "NOUT_P14") (pintype "bidirectional"))
    )
    (net (code "52") (name "Net-(U2-POUT)") (class "Default")
      (node (ref "R6") (pin "2") (pinfunction "2_2") (pintype "passive"))
      (node (ref "U2") (pin "P13") (pinfunction "POUT_P13") (pintype "bidirectional"))
    )
    (net (code "53") (name "Net-(U3-BIASP)") (class "Default")
      (node (ref "C35") (pin "2") (pinfunction "2_2") (pintype "passive"))
      (node (ref "R14") (pin "2") (pinfunction "2_2") (pintype "passive"))
      (node (ref "U3") (pin "P12") (pinfunction "BIASP_P12") (pintype "bidirectional"))
    )
    (net (code "54") (name "Net-(U3-COMP)") (class "Default")
      (node (ref "C37") (pin "2") (pinfunction "2_2") (pintype "passive"))
      (node (ref "U3") (pin "P6") (pinfunction "COMP_P6") (pintype "bidirectional"))
    )
    (net (code "55") (name "Net-(U3-IN+)") (class "Default")
      (node (ref "C44") (pin "2") (pinfunction "2_2") (pintype "passive"))
      (node (ref "R21") (pin "1") (pinfunction "1_1") (pintype "passive"))
      (node (ref "R22") (pin "1") (pinfunction "1_1") (pintype "passive"))
      (node (ref "U3") (pin "P4") (pinfunction "IN+_P4") (pintype "bidirectional"))
    )
    (net (code "56") (name "Net-(U3-IN-)") (class "Default")
      (node (ref "R23") (pin "1") (pinfunction "1_1") (pintype "passive"))
      (node (ref "U3") (pin "P5") (pinfunction "IN-_P5") (pintype "bidirectional"))
      (node (ref "VR5") (pin "A") (pinfunction "A_A") (pintype "passive"))
    )
    (net (code "57") (name "Net-(U3-MUTE)") (class "Default")
      (node (ref "C43") (pin "+") (pinfunction "+_+") (pintype "passive"))
      (node (ref "R20") (pin "2") (pinfunction "2_2") (pintype "passive"))
      (node (ref "U3") (pin "P2") (pinfunction "MUTE_P2") (pintype "bidirectional"))
    )
    (net (code "58") (name "Net-(U3-NOUT)") (class "Default")
      (node (ref "R18") (pin "2") (pinfunction "2_2") (pintype "passive"))
      (node (ref "U3") (pin "P14") (pinfunction "NOUT_P14") (pintype "bidirectional"))
    )
    (net (code "59") (name "Net-(U3-POUT)") (class "Default")
      (node (ref "R17") (pin "2") (pinfunction "2_2") (pintype "passive"))
      (node (ref "U3") (pin "P13") (pinfunction "POUT_P13") (pintype "bidirectional"))
    )
    (net (code "60") (name "V+") (class "Default")
      (node (ref "C11") (pin "1") (pinfunction "1_1") (pintype "passive"))
      (node (ref "C12") (pin "+") (pinfunction "+_+") (pintype "passive"))
      (node (ref "C17") (pin "+") (pinfunction "+_+") (pintype "passive"))
      (node (ref "C19") (pin "1") (pinfunction "1_1") (pintype "passive"))
      (node (ref "C23") (pin "+") (pinfunction "+_+") (pintype "passive"))
      (node (ref "C25") (pin "1") (pinfunction "1_1") (pintype "passive"))
      (node (ref "C32") (pin "+") (pinfunction "+_+") (pintype "passive"))
      (node (ref "C34") (pin "1") (pinfunction "1_1") (pintype "passive"))
      (node (ref "C38") (pin "+") (pinfunction "+_+") (pintype "passive"))
      (node (ref "C4") (pin "+") (pinfunction "+_+") (pintype "passive"))
      (node (ref "C40") (pin "1") (pinfunction "1_1") (pintype "passive"))
      (node (ref "C5") (pin "1") (pinfunction "1_1") (pintype "passive"))
      (node (ref "J10") (pin "P$1") (pinfunction "1_P$1") (pintype "bidirectional"))
      (node (ref "J12") (pin "P$1") (pinfunction "1_P$1") (pintype "bidirectional"))
      (node (ref "J2") (pin "P$4") (pinfunction "4_P$4") (pintype "passive"))
      (node (ref "J6") (pin "P$1") (pinfunction "1_P$1") (pintype "bidirectional"))
      (node (ref "U1") (pin "P15") (pinfunction "+VCC_P15") (pintype "passive"))
      (node (ref "U2") (pin "P15") (pinfunction "+VCC_P15") (pintype "passive"))
      (node (ref "U3") (pin "P15") (pinfunction "+VCC_P15") (pintype "passive"))
    )
    (net (code "61") (name "V-") (class "Default")
      (node (ref "C13") (pin "2") (pinfunction "2_2") (pintype "passive"))
      (node (ref "C14") (pin "-") (pinfunction "-_-") (pintype "passive"))
      (node (ref "C16") (pin "-") (pinfunction "-_-") (pintype "passive"))
      (node (ref "C18") (pin "2") (pinfunction "2_2") (pintype "passive"))
      (node (ref "C2") (pin "-") (pinfunction "-_-") (pintype "passive"))
      (node (ref "C24") (pin "-") (pinfunction "-_-") (pintype "passive"))
      (node (ref "C26") (pin "2") (pinfunction "2_2") (pintype "passive"))
      (node (ref "C3") (pin "2") (pinfunction "2_2") (pintype "passive"))
      (node (ref "C31") (pin "-") (pinfunction "-_-") (pintype "passive"))
      (node (ref "C33") (pin "2") (pinfunction "2_2") (pintype "passive"))
      (node (ref "C39") (pin "-") (pinfunction "-_-") (pintype "passive"))
      (node (ref "C41") (pin "2") (pinfunction "2_2") (pintype "passive"))
      (node (ref "J13") (pin "P$3") (pinfunction "3_P$3") (pintype "bidirectional"))
      (node (ref "J2") (pin "P$3") (pinfunction "3_P$3") (pintype "passive"))
      (node (ref "J8") (pin "P$3") (pinfunction "3_P$3") (pintype "bidirectional"))
      (node (ref "J9") (pin "P$3") (pinfunction "3_P$3") (pintype "bidirectional"))
      (node (ref "U1") (pin "P10") (pinfunction "-VEE_P10") (pintype "power_in"))
      (node (ref "U2") (pin "P10") (pinfunction "-VEE_P10") (pintype "power_in"))
      (node (ref "U3") (pin "P10") (pinfunction "-VEE_P10") (pintype "power_in"))
    )
  )
)
